# bits3_2.net
KiCad netlist of a schematic drawn in EAGLE
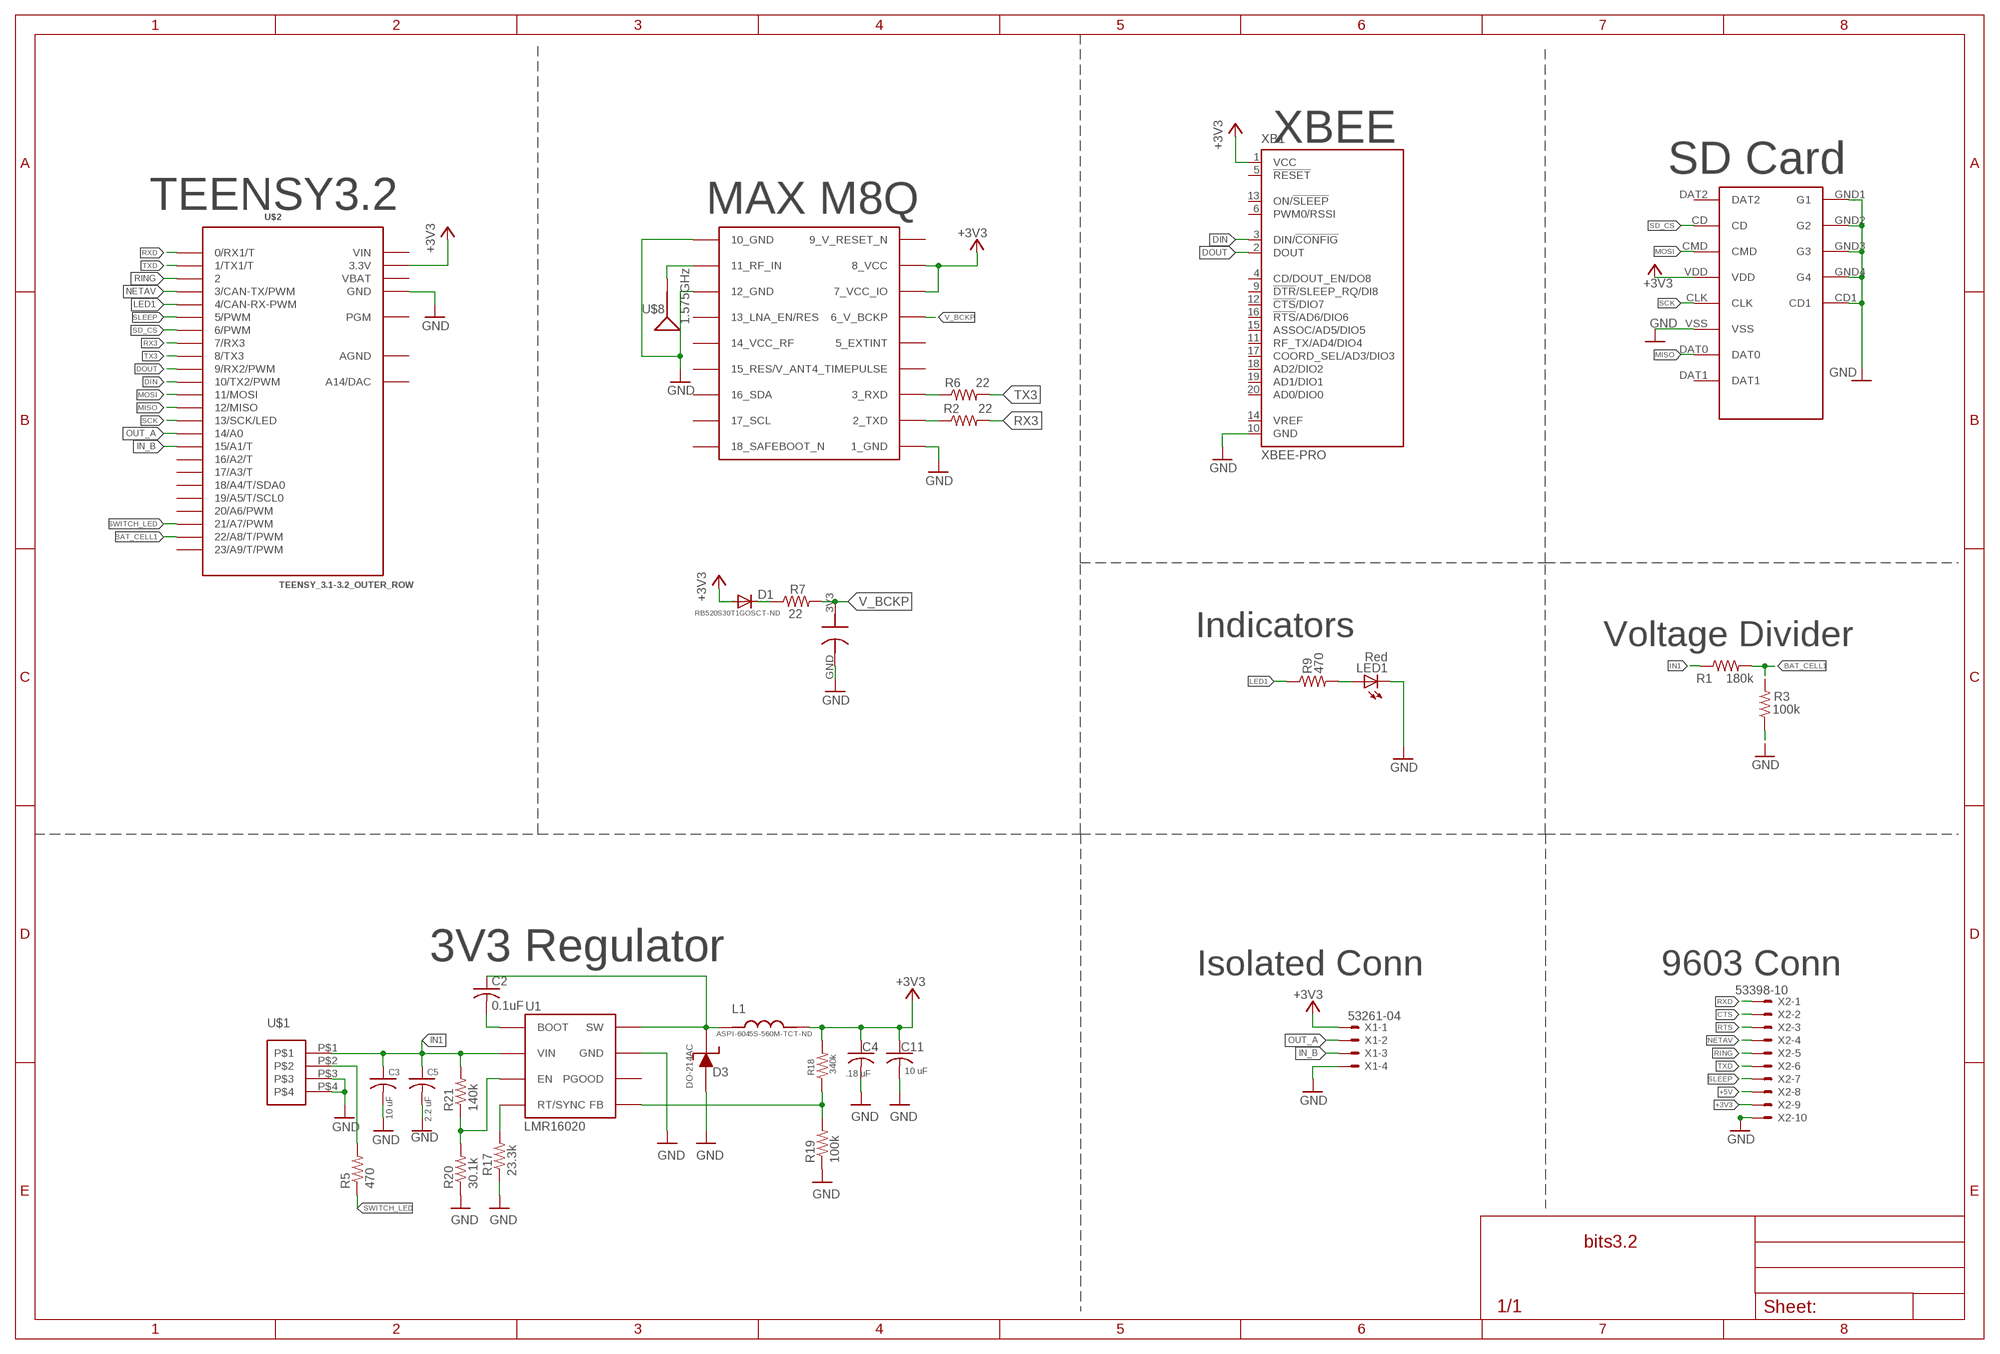
[diagram p0: schematic, sheet 1]

(export (version "E")
  (design (tool "Eeschema 10.0.6"))
  (components
    (comp (ref "C1")
      (value "0.2F")
      (footprint "eagle-import:ELNASUPERCAP")
      (libsource (lib "eagle-import") (part "DCK-3R3E204T614-E"))
    )
    (comp (ref "C2")
      (value "0.1uF")
      (footprint "eagle-import:C0603")
      (libsource (lib "eagle-import") (part "C-USC0603"))
    )
    (comp (ref "C3")
      (value "10 uF")
      (footprint "eagle-import:C1210")
      (libsource (lib "eagle-import") (part "C-USC1210"))
    )
    (comp (ref "C4")
      (value ".18 uF")
      (footprint "eagle-import:C0603")
      (libsource (lib "eagle-import") (part "C-USC0603"))
    )
    (comp (ref "C5")
      (value "2.2 uF")
      (footprint "eagle-import:C1210")
      (libsource (lib "eagle-import") (part "C-USC1210"))
    )
    (comp (ref "C11")
      (value "10 uF")
      (footprint "eagle-import:C0603")
      (libsource (lib "eagle-import") (part "C-USC0603"))
    )
    (comp (ref "D1")
      (value "RB520S30T1GOSCT-ND")
      (footprint "eagle-import:SOD523")
      (libsource (lib "eagle-import") (part "DIODE-SOD523"))
    )
    (comp (ref "D3")
      (value "DO-214AC")
      (footprint "eagle-import:DO-214AC")
      (libsource (lib "eagle-import") (part "DO-214AC"))
    )
    (comp (ref "L1")
      (value "ASPI-6045S-560M-TCT-ND")
      (footprint "eagle-import:ABRACON")
      (libsource (lib "eagle-import") (part "ASPI-6045S-560M-TCT-ND"))
    )
    (comp (ref "LED1")
      (value "Red")
      (footprint "eagle-import:CHIP-LED0603")
      (libsource (lib "eagle-import") (part "LEDCHIP-LED0603"))
    )
    (comp (ref "R1")
      (value "180k")
      (footprint "eagle-import:R0603")
      (libsource (lib "eagle-import") (part "resistor_R-US_R0603"))
    )
    (comp (ref "R2")
      (value "22")
      (footprint "eagle-import:R0603")
      (libsource (lib "eagle-import") (part "R-US_R0603"))
    )
    (comp (ref "R3")
      (value "100k")
      (footprint "eagle-import:R0603")
      (libsource (lib "eagle-import") (part "resistor_R-US_R0603"))
    )
    (comp (ref "R5")
      (value "470")
      (footprint "eagle-import:R0603")
      (libsource (lib "eagle-import") (part "resistor_R-US_R0603"))
    )
    (comp (ref "R6")
      (value "22")
      (footprint "eagle-import:R0603")
      (libsource (lib "eagle-import") (part "R-US_R0603"))
    )
    (comp (ref "R7")
      (value "22")
      (footprint "eagle-import:R0603")
      (libsource (lib "eagle-import") (part "R-US_R0603"))
    )
    (comp (ref "R9")
      (value "470")
      (footprint "eagle-import:R0603")
      (libsource (lib "eagle-import") (part "resistor_R-US_R0603"))
    )
    (comp (ref "R17")
      (value "23.3k")
      (footprint "eagle-import:R0603")
      (libsource (lib "eagle-import") (part "resistor_R-US_R0603"))
    )
    (comp (ref "R18")
      (value "340k")
      (footprint "eagle-import:R0603")
      (libsource (lib "eagle-import") (part "resistor_R-US_R0603"))
    )
    (comp (ref "R19")
      (value "100k")
      (footprint "eagle-import:R0603")
      (libsource (lib "eagle-import") (part "resistor_R-US_R0603"))
    )
    (comp (ref "R20")
      (value "30.1k")
      (footprint "eagle-import:R0603")
      (libsource (lib "eagle-import") (part "resistor_R-US_R0603"))
    )
    (comp (ref "R21")
      (value "140k")
      (footprint "eagle-import:R0603")
      (libsource (lib "eagle-import") (part "resistor_R-US_R0603"))
    )
    (comp (ref "U$1")
      (value "MICROCLASP_4")
      (footprint "eagle-import:4_PIN_MICROCLASP")
      (libsource (lib "eagle-import") (part "MICROCLASP_4"))
    )
    (comp (ref "U$2")
      (value "TEENSY_3.1-3.2_OUTER_ROW")
      (footprint "eagle-import:TEENSY_3.0-3.2&LC_OUTER_ROW")
      (libsource (lib "eagle-import") (part "TEENSY_3.1-3.2_OUTER_ROW"))
    )
    (comp (ref "U$4")
      (value "MICRO_SD")
      (footprint "eagle-import:MICRO_SD_HINGED")
      (libsource (lib "eagle-import") (part "MICRO_SD"))
    )
    (comp (ref "U$7")
      (value "MAX-M8")
      (footprint "eagle-import:MAX-M8")
      (libsource (lib "eagle-import") (part "MAX-M8"))
    )
    (comp (ref "U$8")
      (value "1.575GHz")
      (footprint "eagle-import:SPARKFUN-GPS_ANT-GPS-2X7MM")
      (libsource (lib "eagle-import") (part "SPARKFUN-GPS_ANTENNAGPS-2X7MM"))
    )
    (comp (ref "U1")
      (value "LMR16020")
      (footprint "eagle-import:SO8")
      (libsource (lib "eagle-import") (part "LMR16020"))
    )
    (comp (ref "X1")
      (value "53261-04")
      (footprint "eagle-import:53261-04")
      (fields (field (name "MF") "MOLEX"))
      (libsource (lib "eagle-import") (part "53?-04261"))
    )
    (comp (ref "X2")
      (value "53398-10")
      (footprint "eagle-import:53398-10")
      (fields (field (name "MF") "MOLEX") (field (name "MPN") "53398-1071"))
      (libsource (lib "eagle-import") (part "53?-10398"))
    )
    (comp (ref "XB1")
      (value "XBEE-PRO")
      (footprint "eagle-import:XBEE-PRO")
      (libsource (lib "eagle-import") (part "XBEE-PRO"))
    )
  )
  (nets
    (net (code "1") (name "+3V3") (class "Default")
      (node (ref "C11") (pin "1") (pinfunction "1_1") (pintype "passive"))
      (node (ref "C4") (pin "1") (pinfunction "1_1") (pintype "passive"))
      (node (ref "D1") (pin "A") (pinfunction "A_A") (pintype "passive"))
      (node (ref "L1") (pin "P$2") (pinfunction "P$2_P$2") (pintype "bidirectional"))
      (node (ref "R18") (pin "2") (pinfunction "2_2") (pintype "passive"))
      (node (ref "U$2") (pin "3.3V") (pinfunction "3.3V_3.3V") (pintype "power_in"))
      (node (ref "U$2") (pin "3.3V1") (pinfunction "3.3V_3.3V1") (pintype "power_in"))
      (node (ref "U$4") (pin "VDD") (pinfunction "VDD_VDD") (pintype "bidirectional"))
      (node (ref "U$7") (pin "7_VCC_IO") (pinfunction "7_VCC_IO_7_VCC_IO") (pintype "power_in"))
      (node (ref "U$7") (pin "8_VCC") (pinfunction "8_VCC_8_VCC") (pintype "power_in"))
      (node (ref "X1") (pin "1") (pinfunction "S_1") (pintype "passive"))
      (node (ref "X2") (pin "9") (pinfunction "S_9") (pintype "passive"))
      (node (ref "XB1") (pin "1") (pinfunction "VCC_1") (pintype "power_in"))
    )
    (net (code "2") (name "+5V") (class "Default")
      (node (ref "X2") (pin "8") (pinfunction "S_8") (pintype "passive"))
    )
    (net (code "3") (name "/9_V_RESET_N") (class "Default")
      (node (ref "U$7") (pin "9_RESET_N") (pinfunction "9_V_RESET_N_9_RESET_N") (pintype "power_in"))
    )
    (net (code "4") (name "/AGND") (class "Default")
      (node (ref "U$2") (pin "AGND") (pinfunction "AGND_AGND") (pintype "power_in"))
    )
    (net (code "5") (name "/VBAT") (class "Default")
      (node (ref "U$2") (pin "VBAT") (pinfunction "VBAT_VBAT") (pintype "power_in"))
    )
    (net (code "6") (name "/VIN") (class "Default")
      (node (ref "U$2") (pin "VIN") (pinfunction "VIN_VIN") (pintype "power_in"))
    )
    (net (code "7") (name "BAT_CELL1") (class "Default")
      (node (ref "R1") (pin "2") (pinfunction "2_2") (pintype "passive"))
      (node (ref "R3") (pin "2") (pinfunction "2_2") (pintype "passive"))
      (node (ref "U$2") (pin "22/A8") (pinfunction "22/A8/T/PWM_22/A8") (pintype "bidirectional"))
    )
    (net (code "8") (name "CTS") (class "Default")
      (node (ref "X2") (pin "2") (pinfunction "S_2") (pintype "passive"))
    )
    (net (code "9") (name "DIN") (class "Default")
      (node (ref "U$2") (pin "10") (pinfunction "10/TX2/PWM_10") (pintype "bidirectional"))
      (node (ref "XB1") (pin "3") (pinfunction "DIN/~{CONFIG}_3") (pintype "input"))
    )
    (net (code "10") (name "DOUT") (class "Default")
      (node (ref "U$2") (pin "9") (pinfunction "9/RX2/PWM_9") (pintype "bidirectional"))
      (node (ref "XB1") (pin "2") (pinfunction "DOUT_2") (pintype "output"))
    )
    (net (code "11") (name "GND") (class "Default")
      (node (ref "C1") (pin "GND") (pinfunction "GND_GND") (pintype "bidirectional"))
      (node (ref "C11") (pin "2") (pinfunction "2_2") (pintype "passive"))
      (node (ref "C3") (pin "2") (pinfunction "2_2") (pintype "passive"))
      (node (ref "C4") (pin "2") (pinfunction "2_2") (pintype "passive"))
      (node (ref "C5") (pin "2") (pinfunction "2_2") (pintype "passive"))
      (node (ref "D3") (pin "P$1") (pinfunction "P$1_P$1") (pintype "bidirectional"))
      (node (ref "LED1") (pin "C") (pinfunction "C_C") (pintype "passive"))
      (node (ref "R17") (pin "1") (pinfunction "1_1") (pintype "passive"))
      (node (ref "R19") (pin "1") (pinfunction "1_1") (pintype "passive"))
      (node (ref "R20") (pin "1") (pinfunction "1_1") (pintype "passive"))
      (node (ref "R3") (pin "1") (pinfunction "1_1") (pintype "passive"))
      (node (ref "U$1") (pin "P$3") (pinfunction "P$3_P$3") (pintype "bidirectional"))
      (node (ref "U$1") (pin "P$4") (pinfunction "P$4_P$4") (pintype "bidirectional"))
      (node (ref "U$2") (pin "GND") (pinfunction "GND_GND") (pintype "power_in"))
      (node (ref "U$2") (pin "GND1") (pinfunction "GND_GND1") (pintype "power_in"))
      (node (ref "U$4") (pin "CD1") (pinfunction "CD1_CD1") (pintype "bidirectional"))
      (node (ref "U$4") (pin "GND1") (pinfunction "G1_GND1") (pintype "bidirectional"))
      (node (ref "U$4") (pin "GND2") (pinfunction "G2_GND2") (pintype "bidirectional"))
      (node (ref "U$4") (pin "GND3") (pinfunction "G3_GND3") (pintype "bidirectional"))
      (node (ref "U$4") (pin "GND4") (pinfunction "G4_GND4") (pintype "bidirectional"))
      (node (ref "U$4") (pin "VSS") (pinfunction "VSS_VSS") (pintype "bidirectional"))
      (node (ref "U$7") (pin "10_GND") (pinfunction "10_GND_10_GND") (pintype "power_in"))
      (node (ref "U$7") (pin "12_GND") (pinfunction "12_GND_12_GND") (pintype "power_in"))
      (node (ref "U$7") (pin "1_GND") (pinfunction "1_GND_1_GND") (pintype "power_in"))
      (node (ref "U1") (pin "P$7") (pinfunction "GND_P$7") (pintype "bidirectional"))
      (node (ref "U1") (pin "PAD") (pinfunction "GND_PAD") (pintype "bidirectional"))
      (node (ref "X1") (pin "4") (pinfunction "S_4") (pintype "passive"))
      (node (ref "X2") (pin "10") (pinfunction "S_10") (pintype "passive"))
      (node (ref "XB1") (pin "10") (pinfunction "GND_10") (pintype "power_in"))
    )
    (net (code "12") (name "IN1") (class "Default")
      (node (ref "C3") (pin "1") (pinfunction "1_1") (pintype "passive"))
      (node (ref "C5") (pin "1") (pinfunction "1_1") (pintype "passive"))
      (node (ref "R1") (pin "1") (pinfunction "1_1") (pintype "passive"))
      (node (ref "R21") (pin "2") (pinfunction "2_2") (pintype "passive"))
      (node (ref "U$1") (pin "P$1") (pinfunction "P$1_P$1") (pintype "bidirectional"))
      (node (ref "U1") (pin "P$2") (pinfunction "VIN_P$2") (pintype "bidirectional"))
    )
    (net (code "13") (name "IN_B") (class "Default")
      (node (ref "U$2") (pin "15/A1") (pinfunction "15/A1/T_15/A1") (pintype "bidirectional"))
      (node (ref "X1") (pin "3") (pinfunction "S_3") (pintype "passive"))
    )
    (net (code "14") (name "LED1") (class "Default")
      (node (ref "R9") (pin "1") (pinfunction "1_1") (pintype "passive"))
      (node (ref "U$2") (pin "4") (pinfunction "4/CAN-RX-PWM_4") (pintype "bidirectional"))
    )
    (net (code "15") (name "MISO") (class "Default")
      (node (ref "U$2") (pin "12") (pinfunction "12/MISO_12") (pintype "bidirectional"))
      (node (ref "U$4") (pin "DAT0") (pinfunction "DAT0_DAT0") (pintype "bidirectional"))
    )
    (net (code "16") (name "MOSI") (class "Default")
      (node (ref "U$2") (pin "11") (pinfunction "11/MOSI_11") (pintype "bidirectional"))
      (node (ref "U$4") (pin "CMD") (pinfunction "CMD_CMD") (pintype "bidirectional"))
    )
    (net (code "17") (name "NETAV") (class "Default")
      (node (ref "U$2") (pin "3") (pinfunction "3/CAN-TX/PWM_3") (pintype "bidirectional"))
      (node (ref "X2") (pin "4") (pinfunction "S_4") (pintype "passive"))
    )
    (net (code "18") (name "Net-(D1-PadC)") (class "Default")
      (node (ref "D1") (pin "C") (pinfunction "C_C") (pintype "passive"))
      (node (ref "R7") (pin "1") (pinfunction "1_1") (pintype "passive"))
    )
    (net (code "19") (name "Net-(LED1-PadA)") (class "Default")
      (node (ref "LED1") (pin "A") (pinfunction "A_A") (pintype "passive"))
      (node (ref "R9") (pin "2") (pinfunction "2_2") (pintype "passive"))
    )
    (net (code "20") (name "Net-(R2-Pad1)") (class "Default")
      (node (ref "R2") (pin "1") (pinfunction "1_1") (pintype "passive"))
      (node (ref "U$7") (pin "2_TXD") (pinfunction "2_TXD_2_TXD") (pintype "bidirectional"))
    )
    (net (code "21") (name "Net-(R5-Pad2)") (class "Default")
      (node (ref "R5") (pin "2") (pinfunction "2_2") (pintype "passive"))
      (node (ref "U$1") (pin "P$2") (pinfunction "P$2_P$2") (pintype "bidirectional"))
    )
    (net (code "22") (name "Net-(R6-Pad1)") (class "Default")
      (node (ref "R6") (pin "1") (pinfunction "1_1") (pintype "passive"))
      (node (ref "U$7") (pin "3_RXD") (pinfunction "3_RXD_3_RXD") (pintype "bidirectional"))
    )
    (net (code "23") (name "Net-(U$8-SIGNAL)") (class "Default")
      (node (ref "U$7") (pin "11_RF_IN") (pinfunction "11_RF_IN_11_RF_IN") (pintype "bidirectional"))
      (node (ref "U$8") (pin "1") (pinfunction "SIGNAL_1") (pintype "bidirectional"))
    )
    (net (code "24") (name "Net-(U1-BOOT)") (class "Default")
      (node (ref "C2") (pin "2") (pinfunction "2_2") (pintype "passive"))
      (node (ref "U1") (pin "P$1") (pinfunction "BOOT_P$1") (pintype "bidirectional"))
    )
    (net (code "25") (name "Net-(U1-EN)") (class "Default")
      (node (ref "R20") (pin "2") (pinfunction "2_2") (pintype "passive"))
      (node (ref "R21") (pin "1") (pinfunction "1_1") (pintype "passive"))
      (node (ref "U1") (pin "P$3") (pinfunction "EN_P$3") (pintype "bidirectional"))
    )
    (net (code "26") (name "Net-(U1-FB)") (class "Default")
      (node (ref "R18") (pin "1") (pinfunction "1_1") (pintype "passive"))
      (node (ref "R19") (pin "2") (pinfunction "2_2") (pintype "passive"))
      (node (ref "U1") (pin "P$5") (pinfunction "FB_P$5") (pintype "bidirectional"))
    )
    (net (code "27") (name "Net-(U1-RT{slash}SYNC)") (class "Default")
      (node (ref "R17") (pin "2") (pinfunction "2_2") (pintype "passive"))
      (node (ref "U1") (pin "P$4") (pinfunction "RT/SYNC_P$4") (pintype "bidirectional"))
    )
    (net (code "28") (name "Net-(U1-SW)") (class "Default")
      (node (ref "C2") (pin "1") (pinfunction "1_1") (pintype "passive"))
      (node (ref "D3") (pin "P$2") (pinfunction "P$2_P$2") (pintype "bidirectional"))
      (node (ref "L1") (pin "P$1") (pinfunction "P$1_P$1") (pintype "bidirectional"))
      (node (ref "U1") (pin "P$8") (pinfunction "SW_P$8") (pintype "bidirectional"))
    )
    (net (code "29") (name "OUT_A") (class "Default")
      (node (ref "U$2") (pin "14/A0") (pinfunction "14/A0_14/A0") (pintype "bidirectional"))
      (node (ref "X1") (pin "2") (pinfunction "S_2") (pintype "passive"))
    )
    (net (code "30") (name "RING") (class "Default")
      (node (ref "U$2") (pin "2") (pinfunction "2_2") (pintype "bidirectional"))
      (node (ref "X2") (pin "5") (pinfunction "S_5") (pintype "passive"))
    )
    (net (code "31") (name "RTS") (class "Default")
      (node (ref "X2") (pin "3") (pinfunction "S_3") (pintype "passive"))
    )
    (net (code "32") (name "RX3") (class "Default")
      (node (ref "R2") (pin "2") (pinfunction "2_2") (pintype "passive"))
      (node (ref "U$2") (pin "7") (pinfunction "7/RX3_7") (pintype "bidirectional"))
    )
    (net (code "33") (name "RXD") (class "Default")
      (node (ref "U$2") (pin "0") (pinfunction "0/RX1/T_0") (pintype "bidirectional"))
      (node (ref "X2") (pin "1") (pinfunction "S_1") (pintype "passive"))
    )
    (net (code "34") (name "SCK") (class "Default")
      (node (ref "U$2") (pin "13") (pinfunction "13/SCK/LED_13") (pintype "bidirectional"))
      (node (ref "U$4") (pin "CLK") (pinfunction "CLK_CLK") (pintype "bidirectional"))
    )
    (net (code "35") (name "SD_CS") (class "Default")
      (node (ref "U$2") (pin "6") (pinfunction "6/PWM_6") (pintype "bidirectional"))
      (node (ref "U$4") (pin "CD") (pinfunction "CD_CD") (pintype "bidirectional"))
    )
    (net (code "36") (name "SLEEP") (class "Default")
      (node (ref "U$2") (pin "5") (pinfunction "5/PWM_5") (pintype "bidirectional"))
      (node (ref "X2") (pin "7") (pinfunction "S_7") (pintype "passive"))
    )
    (net (code "37") (name "SWITCH_LED") (class "Default")
      (node (ref "R5") (pin "1") (pinfunction "1_1") (pintype "passive"))
      (node (ref "U$2") (pin "21/A7") (pinfunction "21/A7/PWM_21/A7") (pintype "bidirectional"))
    )
    (net (code "38") (name "TX3") (class "Default")
      (node (ref "R6") (pin "2") (pinfunction "2_2") (pintype "passive"))
      (node (ref "U$2") (pin "8") (pinfunction "8/TX3_8") (pintype "bidirectional"))
    )
    (net (code "39") (name "TXD") (class "Default")
      (node (ref "U$2") (pin "1") (pinfunction "1/TX1/T_1") (pintype "bidirectional"))
      (node (ref "X2") (pin "6") (pinfunction "S_6") (pintype "passive"))
    )
    (net (code "40") (name "V_BCKP") (class "Default")
      (node (ref "C1") (pin "3V3") (pinfunction "3V3_3V3") (pintype "bidirectional"))
      (node (ref "R7") (pin "2") (pinfunction "2_2") (pintype "passive"))
      (node (ref "U$7") (pin "6_V_BCKP") (pinfunction "6_V_BCKP_6_V_BCKP") (pintype "bidirectional"))
    )
    (net (code "41") (name "unconnected-(U$2-16{slash}A2{slash}T-Pad16{slash}A2)") (class "Default")
      (node (ref "U$2") (pin "16/A2") (pinfunction "16/A2/T_16/A2") (pintype "bidirectional"))
    )
    (net (code "42") (name "unconnected-(U$2-17{slash}A3{slash}T-Pad17{slash}A3)") (class "Default")
      (node (ref "U$2") (pin "17/A3") (pinfunction "17/A3/T_17/A3") (pintype "bidirectional"))
    )
    (net (code "43") (name "unconnected-(U$2-18{slash}A4{slash}T{slash}SDA0-Pad18{slash}A4)") (class "Default")
      (node (ref "U$2") (pin "18/A4") (pinfunction "18/A4/T/SDA0_18/A4") (pintype "bidirectional"))
    )
    (net (code "44") (name "unconnected-(U$2-19{slash}A5{slash}T{slash}SCL0-Pad19{slash}A5)") (class "Default")
      (node (ref "U$2") (pin "19/A5") (pinfunction "19/A5/T/SCL0_19/A5") (pintype "bidirectional"))
    )
    (net (code "45") (name "unconnected-(U$2-20{slash}A6{slash}PWM-Pad20{slash}A6)") (class "Default")
      (node (ref "U$2") (pin "20/A6") (pinfunction "20/A6/PWM_20/A6") (pintype "bidirectional"))
    )
    (net (code "46") (name "unconnected-(U$2-23{slash}A9{slash}T{slash}PWM-Pad23{slash}A9)") (class "Default")
      (node (ref "U$2") (pin "23/A9") (pinfunction "23/A9/T/PWM_23/A9") (pintype "bidirectional"))
    )
    (net (code "47") (name "unconnected-(U$2-A14{slash}DAC-PadRESET{slash}DAC)") (class "Default")
      (node (ref "U$2") (pin "RESET/DAC") (pinfunction "A14/DAC_RESET/DAC") (pintype "bidirectional"))
    )
    (net (code "48") (name "unconnected-(U$2-PadPGM)") (class "Default")
      (node (ref "U$2") (pin "PGM") (pinfunction "PGM_PGM") (pintype "bidirectional"))
    )
    (net (code "49") (name "unconnected-(U$4-PadDAT1)") (class "Default")
      (node (ref "U$4") (pin "DAT1") (pinfunction "DAT1_DAT1") (pintype "bidirectional"))
    )
    (net (code "50") (name "unconnected-(U$4-PadDAT2)") (class "Default")
      (node (ref "U$4") (pin "DAT2") (pinfunction "DAT2_DAT2") (pintype "bidirectional"))
    )
    (net (code "51") (name "unconnected-(U$7-13_LNA_EN{slash}RES-Pad13_LNA_EN)") (class "Default")
      (node (ref "U$7") (pin "13_LNA_EN") (pinfunction "13_LNA_EN/RES_13_LNA_EN") (pintype "bidirectional"))
    )
    (net (code "52") (name "unconnected-(U$7-15_RES{slash}V_ANT-Pad15_V_ANT{slash}RESERVED)") (class "Default")
      (node (ref "U$7") (pin "15_V_ANT/RESERVED") (pinfunction "15_RES/V_ANT_15_V_ANT/RESERVED") (pintype "bidirectional"))
    )
    (net (code "53") (name "unconnected-(U$7-Pad4_TIMEPULSE)") (class "Default")
      (node (ref "U$7") (pin "4_TIMEPULSE") (pinfunction "4_TIMEPULSE_4_TIMEPULSE") (pintype "bidirectional"))
    )
    (net (code "54") (name "unconnected-(U$7-Pad5_EXTINT)") (class "Default")
      (node (ref "U$7") (pin "5_EXTINT") (pinfunction "5_EXTINT_5_EXTINT") (pintype "bidirectional"))
    )
    (net (code "55") (name "unconnected-(U$7-Pad14_VCC_RF)") (class "Default")
      (node (ref "U$7") (pin "14_VCC_RF") (pinfunction "14_VCC_RF_14_VCC_RF") (pintype "bidirectional"))
    )
    (net (code "56") (name "unconnected-(U$7-Pad16_SDA)") (class "Default")
      (node (ref "U$7") (pin "16_SDA") (pinfunction "16_SDA_16_SDA") (pintype "bidirectional"))
    )
    (net (code "57") (name "unconnected-(U$7-Pad17_SCL)") (class "Default")
      (node (ref "U$7") (pin "17_SCL") (pinfunction "17_SCL_17_SCL") (pintype "bidirectional"))
    )
    (net (code "58") (name "unconnected-(U$7-Pad18_SAFEBOOT_N)") (class "Default")
      (node (ref "U$7") (pin "18_SAFEBOOT_N") (pinfunction "18_SAFEBOOT_N_18_SAFEBOOT_N") (pintype "bidirectional"))
    )
    (net (code "59") (name "unconnected-(U1-PGOOD-PadP$6)") (class "Default")
      (node (ref "U1") (pin "P$6") (pinfunction "PGOOD_P$6") (pintype "bidirectional"))
    )
    (net (code "60") (name "unconnected-(XB1-AD0{slash}DIO0-Pad20)") (class "Default")
      (node (ref "XB1") (pin "20") (pinfunction "AD0/DIO0_20") (pintype "bidirectional"))
    )
    (net (code "61") (name "unconnected-(XB1-AD1{slash}DIO1-Pad19)") (class "Default")
      (node (ref "XB1") (pin "19") (pinfunction "AD1/DIO1_19") (pintype "bidirectional"))
    )
    (net (code "62") (name "unconnected-(XB1-AD2{slash}DIO2-Pad18)") (class "Default")
      (node (ref "XB1") (pin "18") (pinfunction "AD2/DIO2_18") (pintype "bidirectional"))
    )
    (net (code "63") (name "unconnected-(XB1-ASSOC{slash}AD5{slash}DIO5-Pad15)") (class "Default")
      (node (ref "XB1") (pin "15") (pinfunction "ASSOC/AD5/DIO5_15") (pintype "bidirectional"))
    )
    (net (code "64") (name "unconnected-(XB1-CD{slash}DOUT_EN{slash}DO8-Pad4)") (class "Default")
      (node (ref "XB1") (pin "4") (pinfunction "CD/DOUT_EN/DO8_4") (pintype "output"))
    )
    (net (code "65") (name "unconnected-(XB1-COORD_SEL{slash}AD3{slash}DIO3-Pad17)") (class "Default")
      (node (ref "XB1") (pin "17") (pinfunction "COORD_SEL/AD3/DIO3_17") (pintype "bidirectional"))
    )
    (net (code "66") (name "unconnected-(XB1-ON{slash}~{SLEEP}-Pad13)") (class "Default")
      (node (ref "XB1") (pin "13") (pinfunction "ON/~{SLEEP}_13") (pintype "output"))
    )
    (net (code "67") (name "unconnected-(XB1-PWM0{slash}RSSI-Pad6)") (class "Default")
      (node (ref "XB1") (pin "6") (pinfunction "PWM0/RSSI_6") (pintype "output"))
    )
    (net (code "68") (name "unconnected-(XB1-RF_TX{slash}AD4{slash}DIO4-Pad11)") (class "Default")
      (node (ref "XB1") (pin "11") (pinfunction "RF_TX/AD4/DIO4_11") (pintype "bidirectional"))
    )
    (net (code "69") (name "unconnected-(XB1-VREF-Pad14)") (class "Default")
      (node (ref "XB1") (pin "14") (pinfunction "VREF_14") (pintype "input"))
    )
    (net (code "70") (name "unconnected-(XB1-~{CTS}{slash}DIO7-Pad12)") (class "Default")
      (node (ref "XB1") (pin "12") (pinfunction "~{CTS}/DIO7_12") (pintype "bidirectional"))
    )
    (net (code "71") (name "unconnected-(XB1-~{DTR}{slash}SLEEP_RQ{slash}DI8-Pad9)") (class "Default")
      (node (ref "XB1") (pin "9") (pinfunction "~{DTR}/SLEEP_RQ/DI8_9") (pintype "bidirectional"))
    )
    (net (code "72") (name "unconnected-(XB1-~{RESET}-Pad5)") (class "Default")
      (node (ref "XB1") (pin "5") (pinfunction "~{RESET}_5") (pintype "input"))
    )
    (net (code "73") (name "unconnected-(XB1-~{RTS}{slash}AD6{slash}DIO6-Pad16)") (class "Default")
      (node (ref "XB1") (pin "16") (pinfunction "~{RTS}/AD6/DIO6_16") (pintype "bidirectional"))
    )
  )
)
